# Smarttree_BMS_6.net
KiCad netlist of a schematic drawn in EAGLE
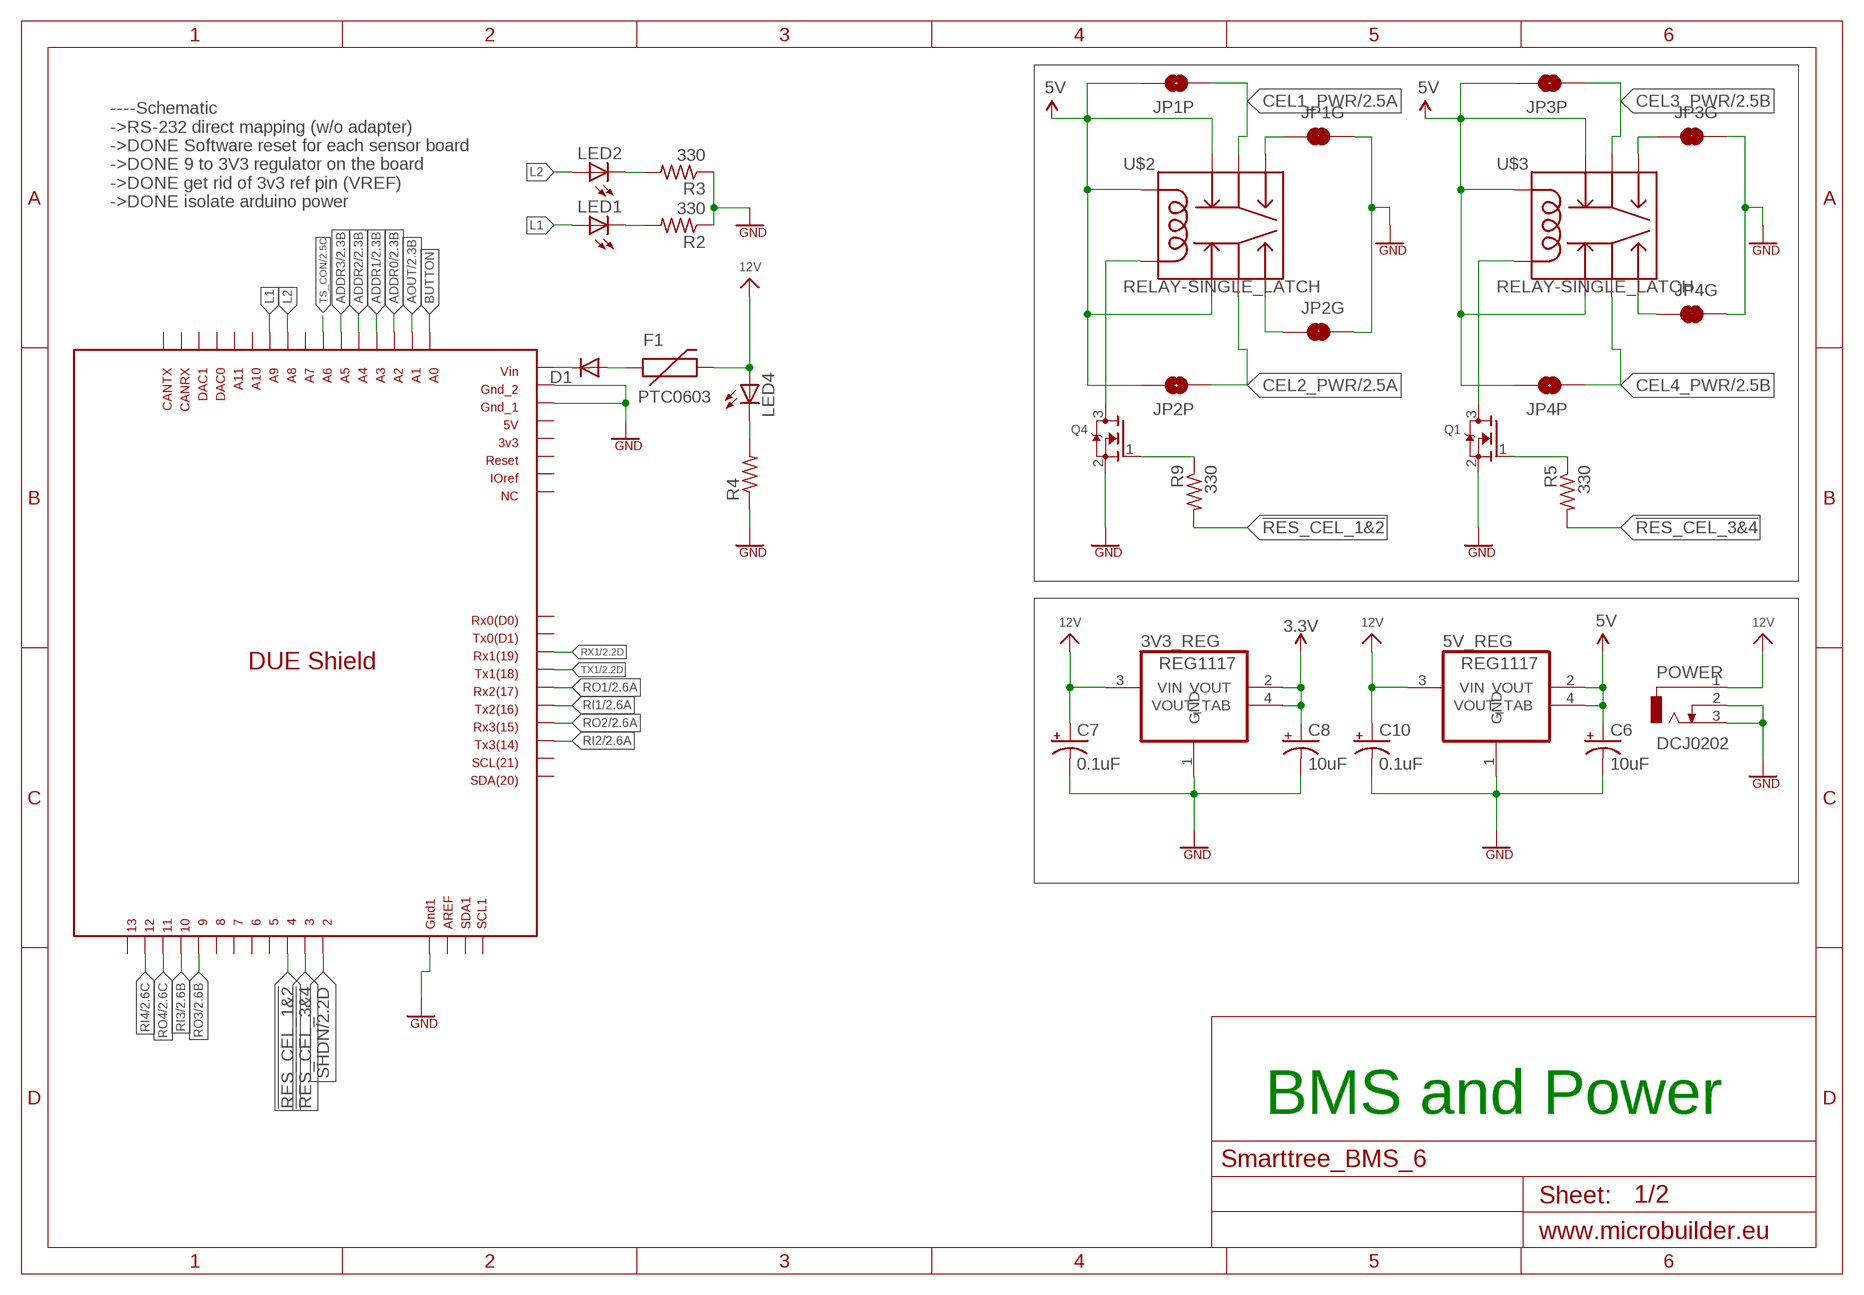
[diagram p0: schematic, sheet 1]
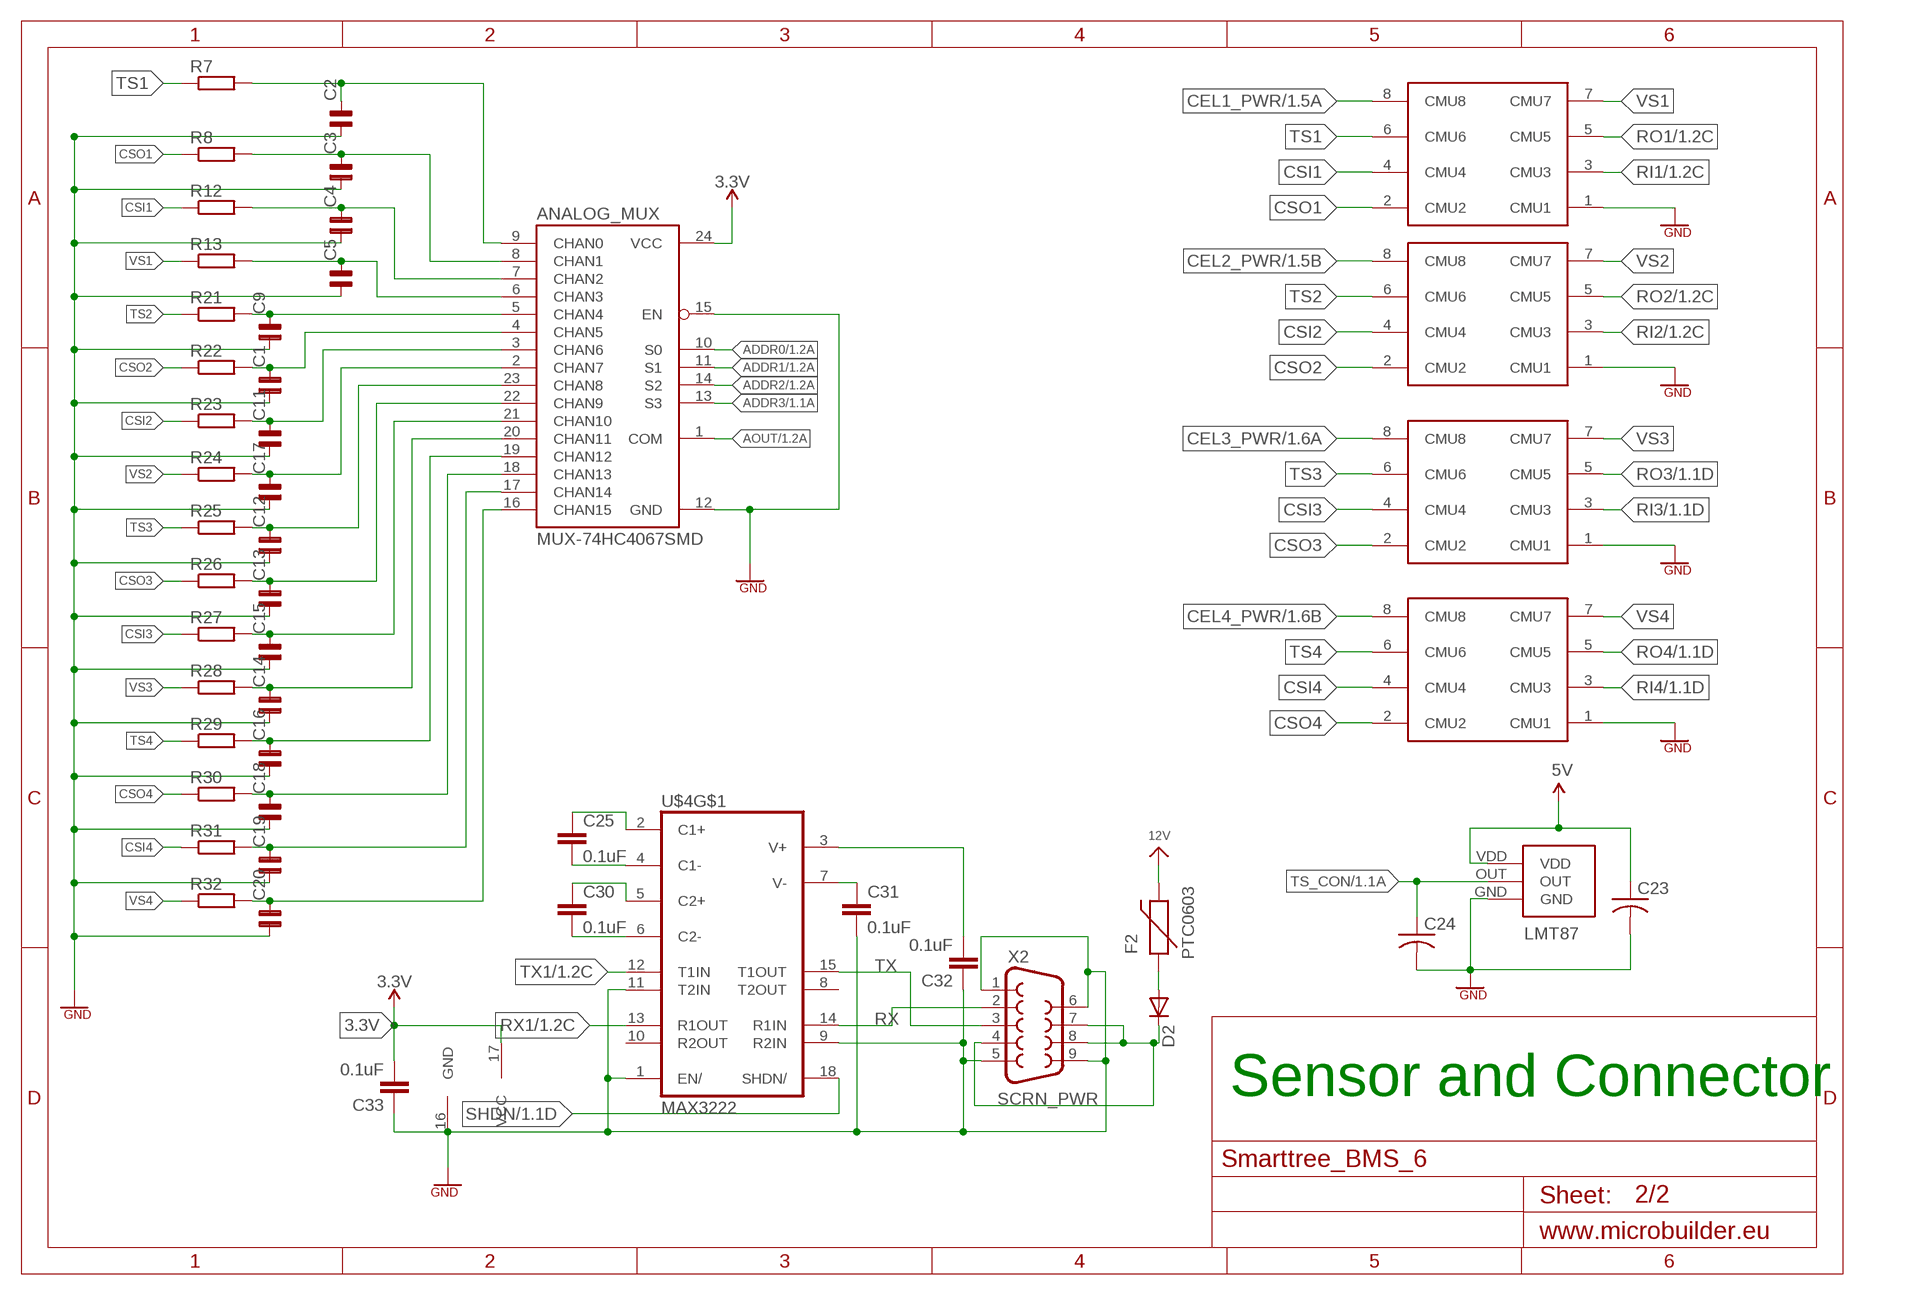
[diagram p1: schematic, sheet 2]

(export (version "E")
  (design (tool "Eeschema 10.0.6"))
  (components
    (comp (ref "ANALOG_MUX")
      (value "MUX-74HC4067SMD")
      (footprint "eagle-import:SSOP24")
      (libsource (lib "eagle-import") (part "MUX-74HC4067SMD"))
    )
    (comp (ref "C1")
      (value "C-NP-SMD-0805")
      (footprint "eagle-import:C-0805")
      (libsource (lib "eagle-import") (part "C-NP-SMD-0805"))
    )
    (comp (ref "C2")
      (value "C-NP-SMD-0805")
      (footprint "eagle-import:C-0805")
      (libsource (lib "eagle-import") (part "C-NP-SMD-0805"))
    )
    (comp (ref "C3")
      (value "C-NP-SMD-0805")
      (footprint "eagle-import:C-0805")
      (libsource (lib "eagle-import") (part "C-NP-SMD-0805"))
    )
    (comp (ref "C4")
      (value "C-NP-SMD-0805")
      (footprint "eagle-import:C-0805")
      (libsource (lib "eagle-import") (part "C-NP-SMD-0805"))
    )
    (comp (ref "C5")
      (value "C-NP-SMD-0805")
      (footprint "eagle-import:C-0805")
      (libsource (lib "eagle-import") (part "C-NP-SMD-0805"))
    )
    (comp (ref "C9")
      (value "C-NP-SMD-0805")
      (footprint "eagle-import:C-0805")
      (libsource (lib "eagle-import") (part "C-NP-SMD-0805"))
    )
    (comp (ref "C11")
      (value "C-NP-SMD-0805")
      (footprint "eagle-import:C-0805")
      (libsource (lib "eagle-import") (part "C-NP-SMD-0805"))
    )
    (comp (ref "C12")
      (value "C-NP-SMD-0805")
      (footprint "eagle-import:C-0805")
      (libsource (lib "eagle-import") (part "C-NP-SMD-0805"))
    )
    (comp (ref "C13")
      (value "C-NP-SMD-0805")
      (footprint "eagle-import:C-0805")
      (libsource (lib "eagle-import") (part "C-NP-SMD-0805"))
    )
    (comp (ref "C14")
      (value "C-NP-SMD-0805")
      (footprint "eagle-import:C-0805")
      (libsource (lib "eagle-import") (part "C-NP-SMD-0805"))
    )
    (comp (ref "C15")
      (value "C-NP-SMD-0805")
      (footprint "eagle-import:C-0805")
      (libsource (lib "eagle-import") (part "C-NP-SMD-0805"))
    )
    (comp (ref "C16")
      (value "C-NP-SMD-0805")
      (footprint "eagle-import:C-0805")
      (libsource (lib "eagle-import") (part "C-NP-SMD-0805"))
    )
    (comp (ref "C17")
      (value "C-NP-SMD-0805")
      (footprint "eagle-import:C-0805")
      (libsource (lib "eagle-import") (part "C-NP-SMD-0805"))
    )
    (comp (ref "C18")
      (value "C-NP-SMD-0805")
      (footprint "eagle-import:C-0805")
      (libsource (lib "eagle-import") (part "C-NP-SMD-0805"))
    )
    (comp (ref "C19")
      (value "C-NP-SMD-0805")
      (footprint "eagle-import:C-0805")
      (libsource (lib "eagle-import") (part "C-NP-SMD-0805"))
    )
    (comp (ref "C20")
      (value "C-NP-SMD-0805")
      (footprint "eagle-import:C-0805")
      (libsource (lib "eagle-import") (part "C-NP-SMD-0805"))
    )
    (comp (ref "C23")
      (value "C-USC0805")
      (footprint "eagle-import:C0805")
      (libsource (lib "eagle-import") (part "C-USC0805"))
    )
    (comp (ref "C24")
      (value "C-USC0805")
      (footprint "eagle-import:C0805")
      (libsource (lib "eagle-import") (part "C-USC0805"))
    )
    (comp (ref "C25")
      (value "0.1uF")
      (footprint "eagle-import:0603-CAP")
      (libsource (lib "eagle-import") (part "CAP0603-CAP"))
    )
    (comp (ref "C30")
      (value "0.1uF")
      (footprint "eagle-import:0603-CAP")
      (libsource (lib "eagle-import") (part "CAP0603-CAP"))
    )
    (comp (ref "C31")
      (value "0.1uF")
      (footprint "eagle-import:0603-CAP")
      (libsource (lib "eagle-import") (part "CAP0603-CAP"))
    )
    (comp (ref "C32")
      (value "0.1uF")
      (footprint "eagle-import:0603-CAP")
      (libsource (lib "eagle-import") (part "CAP0603-CAP"))
    )
    (comp (ref "C33")
      (value "0.1uF")
      (footprint "eagle-import:0603-CAP")
      (libsource (lib "eagle-import") (part "CAP0603-CAP"))
    )
    (comp (ref "CEL1")
      (value "8PINCONN")
      (footprint "eagle-import:8PINCONN")
      (libsource (lib "eagle-import") (part "8PINCONN"))
    )
    (comp (ref "CEL2")
      (value "8PINCONN")
      (footprint "eagle-import:8PINCONN")
      (libsource (lib "eagle-import") (part "8PINCONN"))
    )
    (comp (ref "CEL3")
      (value "8PINCONN")
      (footprint "eagle-import:8PINCONN")
      (libsource (lib "eagle-import") (part "8PINCONN"))
    )
    (comp (ref "CEL4")
      (value "8PINCONN")
      (footprint "eagle-import:8PINCONN")
      (libsource (lib "eagle-import") (part "8PINCONN"))
    )
    (comp (ref "D2")
      (value "DIODE-SOD106-R")
      (footprint "eagle-import:SOD106-R")
      (libsource (lib "eagle-import") (part "DIODE-SOD106-R"))
    )
    (comp (ref "F2")
      (value "PTC0603")
      (footprint "eagle-import:0603")
      (libsource (lib "eagle-import") (part "PTC0603"))
    )
    (comp (ref "LMT87")
      (value "LMT87_PAC")
      (footprint "eagle-import:LMT87_TO")
      (libsource (lib "eagle-import") (part "LMT87_PAC"))
    )
    (comp (ref "R7")
      (value "R-EU_R0805W")
      (footprint "eagle-import:R0805W")
      (libsource (lib "eagle-import") (part "R-EU_R0805W"))
    )
    (comp (ref "R8")
      (value "R-EU_R0805W")
      (footprint "eagle-import:R0805W")
      (libsource (lib "eagle-import") (part "R-EU_R0805W"))
    )
    (comp (ref "R12")
      (value "R-EU_R0805W")
      (footprint "eagle-import:R0805W")
      (libsource (lib "eagle-import") (part "R-EU_R0805W"))
    )
    (comp (ref "R13")
      (value "R-EU_R0805W")
      (footprint "eagle-import:R0805W")
      (libsource (lib "eagle-import") (part "R-EU_R0805W"))
    )
    (comp (ref "R21")
      (value "R-EU_R0805W")
      (footprint "eagle-import:R0805W")
      (libsource (lib "eagle-import") (part "R-EU_R0805W"))
    )
    (comp (ref "R22")
      (value "R-EU_R0805W")
      (footprint "eagle-import:R0805W")
      (libsource (lib "eagle-import") (part "R-EU_R0805W"))
    )
    (comp (ref "R23")
      (value "R-EU_R0805W")
      (footprint "eagle-import:R0805W")
      (libsource (lib "eagle-import") (part "R-EU_R0805W"))
    )
    (comp (ref "R24")
      (value "R-EU_R0805W")
      (footprint "eagle-import:R0805W")
      (libsource (lib "eagle-import") (part "R-EU_R0805W"))
    )
    (comp (ref "R25")
      (value "R-EU_R0805W")
      (footprint "eagle-import:R0805W")
      (libsource (lib "eagle-import") (part "R-EU_R0805W"))
    )
    (comp (ref "R26")
      (value "R-EU_R0805W")
      (footprint "eagle-import:R0805W")
      (libsource (lib "eagle-import") (part "R-EU_R0805W"))
    )
    (comp (ref "R27")
      (value "R-EU_R0805W")
      (footprint "eagle-import:R0805W")
      (libsource (lib "eagle-import") (part "R-EU_R0805W"))
    )
    (comp (ref "R28")
      (value "R-EU_R0805W")
      (footprint "eagle-import:R0805W")
      (libsource (lib "eagle-import") (part "R-EU_R0805W"))
    )
    (comp (ref "R29")
      (value "R-EU_R0805W")
      (footprint "eagle-import:R0805W")
      (libsource (lib "eagle-import") (part "R-EU_R0805W"))
    )
    (comp (ref "R30")
      (value "R-EU_R0805W")
      (footprint "eagle-import:R0805W")
      (libsource (lib "eagle-import") (part "R-EU_R0805W"))
    )
    (comp (ref "R31")
      (value "R-EU_R0805W")
      (footprint "eagle-import:R0805W")
      (libsource (lib "eagle-import") (part "R-EU_R0805W"))
    )
    (comp (ref "R32")
      (value "R-EU_R0805W")
      (footprint "eagle-import:R0805W")
      (libsource (lib "eagle-import") (part "R-EU_R0805W"))
    )
    (comp (ref "U$4")
      (value "MAX3222")
      (footprint "eagle-import:SO18")
      (libsource (lib "eagle-import") (part "MAX3222"))
    )
    (comp (ref "X2")
      (value "DB9MALE")
      (footprint "eagle-import:DB9_MALE")
      (libsource (lib "eagle-import") (part "DB9MALE"))
    )
    (comp (ref "3V3_REG")
      (value "REG1117")
      (footprint "eagle-import:SOT223")
      (libsource (lib "eagle-import") (part "REG1117"))
    )
    (comp (ref "5V_REG")
      (value "REG1117")
      (footprint "eagle-import:SOT223")
      (libsource (lib "eagle-import") (part "REG1117"))
    )
    (comp (ref "C6")
      (value "10uF")
      (footprint "eagle-import:EIA3216")
      (libsource (lib "eagle-import") (part "10UF-TANT"))
    )
    (comp (ref "C7")
      (value "0.1uF")
      (footprint "eagle-import:EIA3216")
      (libsource (lib "eagle-import") (part "10UF-TANT"))
    )
    (comp (ref "C8")
      (value "10uF")
      (footprint "eagle-import:EIA3216")
      (libsource (lib "eagle-import") (part "10UF-TANT"))
    )
    (comp (ref "C10")
      (value "0.1uF")
      (footprint "eagle-import:EIA3216")
      (libsource (lib "eagle-import") (part "10UF-TANT"))
    )
    (comp (ref "D1")
      (value "DIODE-SOD106-R")
      (footprint "eagle-import:SOD106-R")
      (libsource (lib "eagle-import") (part "DIODE-SOD106-R"))
    )
    (comp (ref "F1")
      (value "PTC0603")
      (footprint "eagle-import:0603")
      (libsource (lib "eagle-import") (part "PTC0603"))
    )
    (comp (ref "JP1G")
      (value "JUMPER-SMT_2_NC_TRACE_SILK")
      (footprint "eagle-import:SMT-JUMPER_2_NC_TRACE_SILK")
      (libsource (lib "eagle-import") (part "JUMPER-SMT_2_NC_TRACE_SILK"))
    )
    (comp (ref "JP1P")
      (value "JUMPER-SMT_2_NO_SILK")
      (footprint "eagle-import:SMT-JUMPER_2_NO_SILK")
      (libsource (lib "eagle-import") (part "JUMPER-SMT_2_NO_SILK"))
    )
    (comp (ref "JP2G")
      (value "JUMPER-SMT_2_NC_TRACE_SILK")
      (footprint "eagle-import:SMT-JUMPER_2_NC_TRACE_SILK")
      (libsource (lib "eagle-import") (part "JUMPER-SMT_2_NC_TRACE_SILK"))
    )
    (comp (ref "JP2P")
      (value "JUMPER-SMT_2_NO_SILK")
      (footprint "eagle-import:SMT-JUMPER_2_NO_SILK")
      (libsource (lib "eagle-import") (part "JUMPER-SMT_2_NO_SILK"))
    )
    (comp (ref "JP3G")
      (value "JUMPER-SMT_2_NC_TRACE_SILK")
      (footprint "eagle-import:SMT-JUMPER_2_NC_TRACE_SILK")
      (libsource (lib "eagle-import") (part "JUMPER-SMT_2_NC_TRACE_SILK"))
    )
    (comp (ref "JP3P")
      (value "JUMPER-SMT_2_NO_SILK")
      (footprint "eagle-import:SMT-JUMPER_2_NO_SILK")
      (libsource (lib "eagle-import") (part "JUMPER-SMT_2_NO_SILK"))
    )
    (comp (ref "JP4G")
      (value "JUMPER-SMT_2_NC_TRACE_SILK")
      (footprint "eagle-import:SMT-JUMPER_2_NC_TRACE_SILK")
      (libsource (lib "eagle-import") (part "JUMPER-SMT_2_NC_TRACE_SILK"))
    )
    (comp (ref "JP4P")
      (value "JUMPER-SMT_2_NO_SILK")
      (footprint "eagle-import:SMT-JUMPER_2_NO_SILK")
      (libsource (lib "eagle-import") (part "JUMPER-SMT_2_NO_SILK"))
    )
    (comp (ref "LED1")
      (value "LED-YELLOW0603")
      (footprint "eagle-import:LED-0603")
      (libsource (lib "eagle-import") (part "LED-YELLOW0603"))
    )
    (comp (ref "LED2")
      (value "LED-YELLOW0603")
      (footprint "eagle-import:LED-0603")
      (libsource (lib "eagle-import") (part "LED-YELLOW0603"))
    )
    (comp (ref "LED4")
      (value "LED-YELLOW0603")
      (footprint "eagle-import:LED-0603")
      (libsource (lib "eagle-import") (part "LED-YELLOW0603"))
    )
    (comp (ref "POWER")
      (value "DCJ0202")
      (footprint "eagle-import:DCJ0202")
      (libsource (lib "eagle-import") (part "DCJ0202"))
    )
    (comp (ref "Q1")
      (value "MOSFET-NREFLOW")
      (footprint "eagle-import:SOT23")
      (libsource (lib "eagle-import") (part "MOSFET-NREFLOW"))
    )
    (comp (ref "Q4")
      (value "MOSFET-NREFLOW")
      (footprint "eagle-import:SOT23")
      (libsource (lib "eagle-import") (part "MOSFET-NREFLOW"))
    )
    (comp (ref "R2")
      (value "330")
      (footprint "eagle-import:M0805")
      (libsource (lib "eagle-import") (part "R-US_M0805"))
    )
    (comp (ref "R3")
      (value "330")
      (footprint "eagle-import:M0805")
      (libsource (lib "eagle-import") (part "R-US_M0805"))
    )
    (comp (ref "R4")
      (value "R-US_M0805")
      (footprint "eagle-import:M0805")
      (libsource (lib "eagle-import") (part "R-US_M0805"))
    )
    (comp (ref "R5")
      (value "330")
      (footprint "eagle-import:R0805")
      (libsource (lib "eagle-import") (part "R-US_R0805"))
    )
    (comp (ref "R9")
      (value "330")
      (footprint "eagle-import:R0805")
      (libsource (lib "eagle-import") (part "R-US_R0805"))
    )
    (comp (ref "U$1")
      (value "DUE(OUTLINE)")
      (footprint "eagle-import:DUE(NORMAL)")
      (libsource (lib "eagle-import") (part "DUE(OUTLINE)"))
    )
    (comp (ref "U$2")
      (value "RELAY-SINGLE_LATCH")
      (footprint "eagle-import:RELAY-EE2")
      (libsource (lib "eagle-import") (part "RELAY-SINGLE_LATCH"))
    )
    (comp (ref "U$3")
      (value "RELAY-SINGLE_LATCH")
      (footprint "eagle-import:RELAY-EE2")
      (libsource (lib "eagle-import") (part "RELAY-SINGLE_LATCH"))
    )
  )
  (nets
    (net (code "1") (name "3.3V") (class "Default")
      (node (ref "3V3_REG") (pin "2") (pinfunction "VOUT_2") (pintype "output"))
      (node (ref "3V3_REG") (pin "4") (pinfunction "VOUT_TAB_4") (pintype "bidirectional"))
      (node (ref "ANALOG_MUX") (pin "24") (pinfunction "VCC_24") (pintype "bidirectional"))
      (node (ref "C33") (pin "2") (pinfunction "2_2") (pintype "passive"))
      (node (ref "C8") (pin "A") (pinfunction "+_A") (pintype "passive"))
      (node (ref "U$4") (pin "17") (pinfunction "VCC_17") (pintype "bidirectional"))
    )
    (net (code "2") (name "5V") (class "Default")
      (node (ref "5V_REG") (pin "2") (pinfunction "VOUT_2") (pintype "output"))
      (node (ref "5V_REG") (pin "4") (pinfunction "VOUT_TAB_4") (pintype "bidirectional"))
      (node (ref "C23") (pin "1") (pinfunction "1_1") (pintype "passive"))
      (node (ref "C6") (pin "A") (pinfunction "+_A") (pintype "passive"))
      (node (ref "JP1P") (pin "2") (pinfunction "2_2") (pintype "passive"))
      (node (ref "JP2P") (pin "2") (pinfunction "2_2") (pintype "passive"))
      (node (ref "JP3P") (pin "2") (pinfunction "2_2") (pintype "passive"))
      (node (ref "JP4P") (pin "2") (pinfunction "2_2") (pintype "passive"))
      (node (ref "LMT87") (pin "VDD") (pinfunction "VDD_VDD") (pintype "bidirectional"))
      (node (ref "U$2") (pin "P$1") (pinfunction "COIL1_P$1") (pintype "bidirectional"))
      (node (ref "U$2") (pin "P$10") (pinfunction "P$10_P$10") (pintype "bidirectional"))
      (node (ref "U$2") (pin "P$3") (pinfunction "P$3_P$3") (pintype "bidirectional"))
      (node (ref "U$3") (pin "P$1") (pinfunction "COIL1_P$1") (pintype "bidirectional"))
      (node (ref "U$3") (pin "P$10") (pinfunction "P$10_P$10") (pintype "bidirectional"))
      (node (ref "U$3") (pin "P$3") (pinfunction "P$3_P$3") (pintype "bidirectional"))
    )
    (net (code "3") (name "12V") (class "Default")
      (node (ref "3V3_REG") (pin "3") (pinfunction "VIN_3") (pintype "input"))
      (node (ref "5V_REG") (pin "3") (pinfunction "VIN_3") (pintype "input"))
      (node (ref "C10") (pin "A") (pinfunction "+_A") (pintype "passive"))
      (node (ref "C7") (pin "A") (pinfunction "+_A") (pintype "passive"))
      (node (ref "F1") (pin "2") (pinfunction "2_2") (pintype "bidirectional"))
      (node (ref "F2") (pin "2") (pinfunction "2_2") (pintype "bidirectional"))
      (node (ref "LED4") (pin "A") (pinfunction "A_A") (pintype "passive"))
      (node (ref "POWER") (pin "1") (pinfunction "1_1") (pintype "passive"))
    )
    (net (code "4") (name "ADDR0") (class "Default")
      (node (ref "ANALOG_MUX") (pin "10") (pinfunction "S0_10") (pintype "input"))
      (node (ref "U$1") (pin "A2") (pinfunction "A2_A2") (pintype "bidirectional"))
    )
    (net (code "5") (name "ADDR1") (class "Default")
      (node (ref "ANALOG_MUX") (pin "11") (pinfunction "S1_11") (pintype "input"))
      (node (ref "U$1") (pin "A3") (pinfunction "A3_A3") (pintype "bidirectional"))
    )
    (net (code "6") (name "ADDR2") (class "Default")
      (node (ref "ANALOG_MUX") (pin "14") (pinfunction "S2_14") (pintype "input"))
      (node (ref "U$1") (pin "A4") (pinfunction "A4_A4") (pintype "bidirectional"))
    )
    (net (code "7") (name "ADDR3") (class "Default")
      (node (ref "ANALOG_MUX") (pin "13") (pinfunction "S3_13") (pintype "input"))
      (node (ref "U$1") (pin "A5") (pinfunction "A5_A5") (pintype "bidirectional"))
    )
    (net (code "8") (name "AOUT") (class "Default")
      (node (ref "ANALOG_MUX") (pin "1") (pinfunction "COM_1") (pintype "bidirectional"))
      (node (ref "U$1") (pin "A1") (pinfunction "A1_A1") (pintype "bidirectional"))
    )
    (net (code "9") (name "BUTTON") (class "Default")
      (node (ref "U$1") (pin "A0") (pinfunction "A0_A0") (pintype "bidirectional"))
    )
    (net (code "10") (name "CEL1_PWR") (class "Default")
      (node (ref "CEL1") (pin "8") (pinfunction "CMU8_8") (pintype "bidirectional"))
      (node (ref "JP1P") (pin "1") (pinfunction "1_1") (pintype "passive"))
      (node (ref "U$2") (pin "P$4") (pinfunction "P$4_P$4") (pintype "bidirectional"))
    )
    (net (code "11") (name "CEL2_PWR") (class "Default")
      (node (ref "CEL2") (pin "8") (pinfunction "CMU8_8") (pintype "bidirectional"))
      (node (ref "JP2P") (pin "1") (pinfunction "1_1") (pintype "passive"))
      (node (ref "U$2") (pin "P$9") (pinfunction "P$9_P$9") (pintype "bidirectional"))
    )
    (net (code "12") (name "CEL3_PWR") (class "Default")
      (node (ref "CEL3") (pin "8") (pinfunction "CMU8_8") (pintype "bidirectional"))
      (node (ref "JP3P") (pin "1") (pinfunction "1_1") (pintype "passive"))
      (node (ref "U$3") (pin "P$4") (pinfunction "P$4_P$4") (pintype "bidirectional"))
    )
    (net (code "13") (name "CEL4_PWR") (class "Default")
      (node (ref "CEL4") (pin "8") (pinfunction "CMU8_8") (pintype "bidirectional"))
      (node (ref "JP4P") (pin "1") (pinfunction "1_1") (pintype "passive"))
      (node (ref "U$3") (pin "P$9") (pinfunction "P$9_P$9") (pintype "bidirectional"))
    )
    (net (code "14") (name "CSI1") (class "Default")
      (node (ref "CEL1") (pin "4") (pinfunction "CMU4_4") (pintype "bidirectional"))
      (node (ref "R12") (pin "1") (pinfunction "1_1") (pintype "passive"))
    )
    (net (code "15") (name "CSI2") (class "Default")
      (node (ref "CEL2") (pin "4") (pinfunction "CMU4_4") (pintype "bidirectional"))
      (node (ref "R23") (pin "1") (pinfunction "1_1") (pintype "passive"))
    )
    (net (code "16") (name "CSI3") (class "Default")
      (node (ref "CEL3") (pin "4") (pinfunction "CMU4_4") (pintype "bidirectional"))
      (node (ref "R27") (pin "1") (pinfunction "1_1") (pintype "passive"))
    )
    (net (code "17") (name "CSI4") (class "Default")
      (node (ref "CEL4") (pin "4") (pinfunction "CMU4_4") (pintype "bidirectional"))
      (node (ref "R31") (pin "1") (pinfunction "1_1") (pintype "passive"))
    )
    (net (code "18") (name "CSO1") (class "Default")
      (node (ref "CEL1") (pin "2") (pinfunction "CMU2_2") (pintype "bidirectional"))
      (node (ref "R8") (pin "1") (pinfunction "1_1") (pintype "passive"))
    )
    (net (code "19") (name "CSO2") (class "Default")
      (node (ref "CEL2") (pin "2") (pinfunction "CMU2_2") (pintype "bidirectional"))
      (node (ref "R22") (pin "1") (pinfunction "1_1") (pintype "passive"))
    )
    (net (code "20") (name "CSO3") (class "Default")
      (node (ref "CEL3") (pin "2") (pinfunction "CMU2_2") (pintype "bidirectional"))
      (node (ref "R26") (pin "1") (pinfunction "1_1") (pintype "passive"))
    )
    (net (code "21") (name "CSO4") (class "Default")
      (node (ref "CEL4") (pin "2") (pinfunction "CMU2_2") (pintype "bidirectional"))
      (node (ref "R30") (pin "1") (pinfunction "1_1") (pintype "passive"))
    )
    (net (code "22") (name "GND") (class "Default")
      (node (ref "3V3_REG") (pin "1") (pinfunction "GND_1") (pintype "power_in"))
      (node (ref "5V_REG") (pin "1") (pinfunction "GND_1") (pintype "power_in"))
      (node (ref "ANALOG_MUX") (pin "12") (pinfunction "GND_12") (pintype "bidirectional"))
      (node (ref "ANALOG_MUX") (pin "15") (pinfunction "EN_15") (pintype "input"))
      (node (ref "C1") (pin "1") (pinfunction "1_1") (pintype "passive"))
      (node (ref "C10") (pin "C") (pinfunction "-_C") (pintype "passive"))
      (node (ref "C11") (pin "1") (pinfunction "1_1") (pintype "passive"))
      (node (ref "C12") (pin "1") (pinfunction "1_1") (pintype "passive"))
      (node (ref "C13") (pin "1") (pinfunction "1_1") (pintype "passive"))
      (node (ref "C14") (pin "1") (pinfunction "1_1") (pintype "passive"))
      (node (ref "C15") (pin "1") (pinfunction "1_1") (pintype "passive"))
      (node (ref "C16") (pin "1") (pinfunction "1_1") (pintype "passive"))
      (node (ref "C17") (pin "1") (pinfunction "1_1") (pintype "passive"))
      (node (ref "C18") (pin "1") (pinfunction "1_1") (pintype "passive"))
      (node (ref "C19") (pin "1") (pinfunction "1_1") (pintype "passive"))
      (node (ref "C2") (pin "1") (pinfunction "1_1") (pintype "passive"))
      (node (ref "C20") (pin "1") (pinfunction "1_1") (pintype "passive"))
      (node (ref "C23") (pin "2") (pinfunction "2_2") (pintype "passive"))
      (node (ref "C24") (pin "2") (pinfunction "2_2") (pintype "passive"))
      (node (ref "C3") (pin "1") (pinfunction "1_1") (pintype "passive"))
      (node (ref "C31") (pin "2") (pinfunction "2_2") (pintype "passive"))
      (node (ref "C32") (pin "1") (pinfunction "1_1") (pintype "passive"))
      (node (ref "C33") (pin "1") (pinfunction "1_1") (pintype "passive"))
      (node (ref "C4") (pin "1") (pinfunction "1_1") (pintype "passive"))
      (node (ref "C5") (pin "1") (pinfunction "1_1") (pintype "passive"))
      (node (ref "C6") (pin "C") (pinfunction "-_C") (pintype "passive"))
      (node (ref "C7") (pin "C") (pinfunction "-_C") (pintype "passive"))
      (node (ref "C8") (pin "C") (pinfunction "-_C") (pintype "passive"))
      (node (ref "C9") (pin "1") (pinfunction "1_1") (pintype "passive"))
      (node (ref "CEL1") (pin "1") (pinfunction "CMU1_1") (pintype "bidirectional"))
      (node (ref "CEL2") (pin "1") (pinfunction "CMU1_1") (pintype "bidirectional"))
      (node (ref "CEL3") (pin "1") (pinfunction "CMU1_1") (pintype "bidirectional"))
      (node (ref "CEL4") (pin "1") (pinfunction "CMU1_1") (pintype "bidirectional"))
      (node (ref "JP1G") (pin "2") (pinfunction "2_2") (pintype "passive"))
      (node (ref "JP2G") (pin "2") (pinfunction "2_2") (pintype "passive"))
      (node (ref "JP3G") (pin "2") (pinfunction "2_2") (pintype "passive"))
      (node (ref "JP4G") (pin "2") (pinfunction "2_2") (pintype "passive"))
      (node (ref "LMT87") (pin "GND") (pinfunction "GND_GND") (pintype "bidirectional"))
      (node (ref "POWER") (pin "2") (pinfunction "2_2") (pintype "passive"))
      (node (ref "POWER") (pin "3") (pinfunction "3_3") (pintype "passive"))
      (node (ref "Q1") (pin "2") (pinfunction "S_2") (pintype "bidirectional"))
      (node (ref "Q4") (pin "2") (pinfunction "S_2") (pintype "bidirectional"))
      (node (ref "R2") (pin "1") (pinfunction "1_1") (pintype "passive"))
      (node (ref "R3") (pin "1") (pinfunction "1_1") (pintype "passive"))
      (node (ref "R4") (pin "1") (pinfunction "1_1") (pintype "passive"))
      (node (ref "U$1") (pin "GND1") (pinfunction "GND1_GND1") (pintype "bidirectional"))
      (node (ref "U$1") (pin "GND_1") (pinfunction "GND_1_GND_1") (pintype "bidirectional"))
      (node (ref "U$1") (pin "GND_2") (pinfunction "GND_2_GND_2") (pintype "bidirectional"))
      (node (ref "U$4") (pin "1") (pinfunction "EN/_1") (pintype "input"))
      (node (ref "U$4") (pin "11") (pinfunction "T2IN_11") (pintype "input"))
      (node (ref "U$4") (pin "16") (pinfunction "GND_16") (pintype "bidirectional"))
      (node (ref "U$4") (pin "9") (pinfunction "R2IN_9") (pintype "input"))
      (node (ref "X2") (pin "1") (pinfunction "1_1") (pintype "passive"))
      (node (ref "X2") (pin "5") (pinfunction "5_5") (pintype "passive"))
      (node (ref "X2") (pin "6") (pinfunction "6_6") (pintype "passive"))
      (node (ref "X2") (pin "9") (pinfunction "9_9") (pintype "passive"))
    )
    (net (code "23") (name "L1") (class "Default")
      (node (ref "LED1") (pin "A") (pinfunction "A_A") (pintype "passive"))
      (node (ref "U$1") (pin "A9") (pinfunction "A9_A9") (pintype "bidirectional"))
    )
    (net (code "24") (name "L2") (class "Default")
      (node (ref "LED2") (pin "A") (pinfunction "A_A") (pintype "passive"))
      (node (ref "U$1") (pin "A8") (pinfunction "A8_A8") (pintype "bidirectional"))
    )
    (net (code "25") (name "Net-(ANALOG_MUX-CHAN0)") (class "Default")
      (node (ref "ANALOG_MUX") (pin "9") (pinfunction "CHAN0_9") (pintype "bidirectional"))
      (node (ref "C2") (pin "2") (pinfunction "2_2") (pintype "passive"))
      (node (ref "R7") (pin "2") (pinfunction "2_2") (pintype "passive"))
    )
    (net (code "26") (name "Net-(ANALOG_MUX-CHAN1)") (class "Default")
      (node (ref "ANALOG_MUX") (pin "8") (pinfunction "CHAN1_8") (pintype "bidirectional"))
      (node (ref "C3") (pin "2") (pinfunction "2_2") (pintype "passive"))
      (node (ref "R8") (pin "2") (pinfunction "2_2") (pintype "passive"))
    )
    (net (code "27") (name "Net-(ANALOG_MUX-CHAN2)") (class "Default")
      (node (ref "ANALOG_MUX") (pin "7") (pinfunction "CHAN2_7") (pintype "bidirectional"))
      (node (ref "C4") (pin "2") (pinfunction "2_2") (pintype "passive"))
      (node (ref "R12") (pin "2") (pinfunction "2_2") (pintype "passive"))
    )
    (net (code "28") (name "Net-(ANALOG_MUX-CHAN3)") (class "Default")
      (node (ref "ANALOG_MUX") (pin "6") (pinfunction "CHAN3_6") (pintype "bidirectional"))
      (node (ref "C5") (pin "2") (pinfunction "2_2") (pintype "passive"))
      (node (ref "R13") (pin "2") (pinfunction "2_2") (pintype "passive"))
    )
    (net (code "29") (name "Net-(ANALOG_MUX-CHAN4)") (class "Default")
      (node (ref "ANALOG_MUX") (pin "5") (pinfunction "CHAN4_5") (pintype "bidirectional"))
      (node (ref "C9") (pin "2") (pinfunction "2_2") (pintype "passive"))
      (node (ref "R21") (pin "2") (pinfunction "2_2") (pintype "passive"))
    )
    (net (code "30") (name "Net-(ANALOG_MUX-CHAN5)") (class "Default")
      (node (ref "ANALOG_MUX") (pin "4") (pinfunction "CHAN5_4") (pintype "bidirectional"))
      (node (ref "C1") (pin "2") (pinfunction "2_2") (pintype "passive"))
      (node (ref "R22") (pin "2") (pinfunction "2_2") (pintype "passive"))
    )
    (net (code "31") (name "Net-(ANALOG_MUX-CHAN6)") (class "Default")
      (node (ref "ANALOG_MUX") (pin "3") (pinfunction "CHAN6_3") (pintype "bidirectional"))
      (node (ref "C11") (pin "2") (pinfunction "2_2") (pintype "passive"))
      (node (ref "R23") (pin "2") (pinfunction "2_2") (pintype "passive"))
    )
    (net (code "32") (name "Net-(ANALOG_MUX-CHAN7)") (class "Default")
      (node (ref "ANALOG_MUX") (pin "2") (pinfunction "CHAN7_2") (pintype "bidirectional"))
      (node (ref "C17") (pin "2") (pinfunction "2_2") (pintype "passive"))
      (node (ref "R24") (pin "2") (pinfunction "2_2") (pintype "passive"))
    )
    (net (code "33") (name "Net-(ANALOG_MUX-CHAN8)") (class "Default")
      (node (ref "ANALOG_MUX") (pin "23") (pinfunction "CHAN8_23") (pintype "bidirectional"))
      (node (ref "C12") (pin "2") (pinfunction "2_2") (pintype "passive"))
      (node (ref "R25") (pin "2") (pinfunction "2_2") (pintype "passive"))
    )
    (net (code "34") (name "Net-(ANALOG_MUX-CHAN9)") (class "Default")
      (node (ref "ANALOG_MUX") (pin "22") (pinfunction "CHAN9_22") (pintype "bidirectional"))
      (node (ref "C13") (pin "2") (pinfunction "2_2") (pintype "passive"))
      (node (ref "R26") (pin "2") (pinfunction "2_2") (pintype "passive"))
    )
    (net (code "35") (name "Net-(ANALOG_MUX-CHAN10)") (class "Default")
      (node (ref "ANALOG_MUX") (pin "21") (pinfunction "CHAN10_21") (pintype "bidirectional"))
      (node (ref "C15") (pin "2") (pinfunction "2_2") (pintype "passive"))
      (node (ref "R27") (pin "2") (pinfunction "2_2") (pintype "passive"))
    )
    (net (code "36") (name "Net-(ANALOG_MUX-CHAN11)") (class "Default")
      (node (ref "ANALOG_MUX") (pin "20") (pinfunction "CHAN11_20") (pintype "bidirectional"))
      (node (ref "C14") (pin "2") (pinfunction "2_2") (pintype "passive"))
      (node (ref "R28") (pin "2") (pinfunction "2_2") (pintype "passive"))
    )
    (net (code "37") (name "Net-(ANALOG_MUX-CHAN12)") (class "Default")
      (node (ref "ANALOG_MUX") (pin "19") (pinfunction "CHAN12_19") (pintype "bidirectional"))
      (node (ref "C16") (pin "2") (pinfunction "2_2") (pintype "passive"))
      (node (ref "R29") (pin "2") (pinfunction "2_2") (pintype "passive"))
    )
    (net (code "38") (name "Net-(ANALOG_MUX-CHAN13)") (class "Default")
      (node (ref "ANALOG_MUX") (pin "18") (pinfunction "CHAN13_18") (pintype "bidirectional"))
      (node (ref "C18") (pin "2") (pinfunction "2_2") (pintype "passive"))
      (node (ref "R30") (pin "2") (pinfunction "2_2") (pintype "passive"))
    )
    (net (code "39") (name "Net-(ANALOG_MUX-CHAN14)") (class "Default")
      (node (ref "ANALOG_MUX") (pin "17") (pinfunction "CHAN14_17") (pintype "bidirectional"))
      (node (ref "C19") (pin "2") (pinfunction "2_2") (pintype "passive"))
      (node (ref "R31") (pin "2") (pinfunction "2_2") (pintype "passive"))
    )
    (net (code "40") (name "Net-(ANALOG_MUX-CHAN15)") (class "Default")
      (node (ref "ANALOG_MUX") (pin "16") (pinfunction "CHAN15_16") (pintype "bidirectional"))
      (node (ref "C20") (pin "2") (pinfunction "2_2") (pintype "passive"))
      (node (ref "R32") (pin "2") (pinfunction "2_2") (pintype "passive"))
    )
    (net (code "41") (name "Net-(D1-PadA)") (class "Default")
      (node (ref "D1") (pin "A") (pinfunction "A_A") (pintype "passive"))
      (node (ref "F1") (pin "1") (pinfunction "1_1") (pintype "bidirectional"))
    )
    (net (code "42") (name "Net-(D1-PadC)") (class "Default")
      (node (ref "D1") (pin "C") (pinfunction "C_C") (pintype "passive"))
      (node (ref "U$1") (pin "VIN") (pinfunction "VIN_VIN") (pintype "bidirectional"))
    )
    (net (code "43") (name "Net-(D2-PadA)") (class "Default")
      (node (ref "D2") (pin "A") (pinfunction "A_A") (pintype "passive"))
      (node (ref "F2") (pin "1") (pinfunction "1_1") (pintype "bidirectional"))
    )
    (net (code "44") (name "Net-(JP1G-Pad1)") (class "Default")
      (node (ref "JP1G") (pin "1") (pinfunction "1_1") (pintype "passive"))
      (node (ref "U$2") (pin "P$5") (pinfunction "P$5_P$5") (pintype "bidirectional"))
    )
    (net (code "45") (name "Net-(JP2G-Pad1)") (class "Default")
      (node (ref "JP2G") (pin "1") (pinfunction "1_1") (pintype "passive"))
      (node (ref "U$2") (pin "P$8") (pinfunction "P$8_P$8") (pintype "bidirectional"))
    )
    (net (code "46") (name "Net-(JP3G-Pad1)") (class "Default")
      (node (ref "JP3G") (pin "1") (pinfunction "1_1") (pintype "passive"))
      (node (ref "U$3") (pin "P$5") (pinfunction "P$5_P$5") (pintype "bidirectional"))
    )
    (net (code "47") (name "Net-(JP4G-Pad1)") (class "Default")
      (node (ref "JP4G") (pin "1") (pinfunction "1_1") (pintype "passive"))
      (node (ref "U$3") (pin "P$8") (pinfunction "P$8_P$8") (pintype "bidirectional"))
    )
    (net (code "48") (name "Net-(LED1-PadC)") (class "Default")
      (node (ref "LED1") (pin "C") (pinfunction "C_C") (pintype "passive"))
      (node (ref "R2") (pin "2") (pinfunction "2_2") (pintype "passive"))
    )
    (net (code "49") (name "Net-(LED2-PadC)") (class "Default")
      (node (ref "LED2") (pin "C") (pinfunction "C_C") (pintype "passive"))
      (node (ref "R3") (pin "2") (pinfunction "2_2") (pintype "passive"))
    )
    (net (code "50") (name "Net-(LED4-PadC)") (class "Default")
      (node (ref "LED4") (pin "C") (pinfunction "C_C") (pintype "passive"))
      (node (ref "R4") (pin "2") (pinfunction "2_2") (pintype "passive"))
    )
    (net (code "51") (name "Net-(Q1-D)") (class "Default")
      (node (ref "Q1") (pin "3") (pinfunction "D_3") (pintype "bidirectional"))
      (node (ref "U$3") (pin "P$12") (pinfunction "COIL12_P$12") (pintype "bidirectional"))
    )
    (net (code "52") (name "Net-(Q1-G)") (class "Default")
      (node (ref "Q1") (pin "1") (pinfunction "G_1") (pintype "bidirectional"))
      (node (ref "R5") (pin "1") (pinfunction "1_1") (pintype "passive"))
    )
    (net (code "53") (name "Net-(Q4-D)") (class "Default")
      (node (ref "Q4") (pin "3") (pinfunction "D_3") (pintype "bidirectional"))
      (node (ref "U$2") (pin "P$12") (pinfunction "COIL12_P$12") (pintype "bidirectional"))
    )
    (net (code "54") (name "Net-(Q4-G)") (class "Default")
      (node (ref "Q4") (pin "1") (pinfunction "G_1") (pintype "bidirectional"))
      (node (ref "R9") (pin "1") (pinfunction "1_1") (pintype "passive"))
    )
    (net (code "55") (name "Net-(U$4A-C1+)") (class "Default")
      (node (ref "C25") (pin "1") (pinfunction "1_1") (pintype "passive"))
      (node (ref "U$4") (pin "2") (pinfunction "C1+_2") (pintype "passive"))
    )
    (net (code "56") (name "Net-(U$4A-C1-)") (class "Default")
      (node (ref "C25") (pin "2") (pinfunction "2_2") (pintype "passive"))
      (node (ref "U$4") (pin "4") (pinfunction "C1-_4") (pintype "passive"))
    )
    (net (code "57") (name "Net-(U$4A-C2+)") (class "Default")
      (node (ref "C30") (pin "1") (pinfunction "1_1") (pintype "passive"))
      (node (ref "U$4") (pin "5") (pinfunction "C2+_5") (pintype "passive"))
    )
    (net (code "58") (name "Net-(U$4A-C2-)") (class "Default")
      (node (ref "C30") (pin "2") (pinfunction "2_2") (pintype "passive"))
      (node (ref "U$4") (pin "6") (pinfunction "C2-_6") (pintype "passive"))
    )
    (net (code "59") (name "Net-(U$4A-V+)") (class "Default")
      (node (ref "C32") (pin "2") (pinfunction "2_2") (pintype "passive"))
      (node (ref "U$4") (pin "3") (pinfunction "V+_3") (pintype "passive"))
    )
    (net (code "60") (name "Net-(U$4A-V-)") (class "Default")
      (node (ref "C31") (pin "1") (pinfunction "1_1") (pintype "passive"))
      (node (ref "U$4") (pin "7") (pinfunction "V-_7") (pintype "passive"))
    )
    (net (code "61") (name "RI1") (class "Default")
      (node (ref "CEL1") (pin "3") (pinfunction "CMU3_3") (pintype "bidirectional"))
      (node (ref "U$1") (pin "TX2") (pinfunction "TX2_TX2") (pintype "bidirectional"))
    )
    (net (code "62") (name "RI2") (class "Default")
      (node (ref "CEL2") (pin "3") (pinfunction "CMU3_3") (pintype "bidirectional"))
      (node (ref "U$1") (pin "TX3") (pinfunction "TX3_TX3") (pintype "bidirectional"))
    )
    (net (code "63") (name "RI3") (class "Default")
      (node (ref "CEL3") (pin "3") (pinfunction "CMU3_3") (pintype "bidirectional"))
      (node (ref "U$1") (pin "10") (pinfunction "10_10") (pintype "bidirectional"))
    )
    (net (code "64") (name "RI4") (class "Default")
      (node (ref "CEL4") (pin "3") (pinfunction "CMU3_3") (pintype "bidirectional"))
      (node (ref "U$1") (pin "12") (pinfunction "12_12") (pintype "bidirectional"))
    )
    (net (code "65") (name "RO1") (class "Default")
      (node (ref "CEL1") (pin "5") (pinfunction "CMU5_5") (pintype "bidirectional"))
      (node (ref "U$1") (pin "RX2") (pinfunction "RX2_RX2") (pintype "bidirectional"))
    )
    (net (code "66") (name "RO2") (class "Default")
      (node (ref "CEL2") (pin "5") (pinfunction "CMU5_5") (pintype "bidirectional"))
      (node (ref "U$1") (pin "RX3") (pinfunction "RX3_RX3") (pintype "bidirectional"))
    )
    (net (code "67") (name "RO3") (class "Default")
      (node (ref "CEL3") (pin "5") (pinfunction "CMU5_5") (pintype "bidirectional"))
      (node (ref "U$1") (pin "9") (pinfunction "9_9") (pintype "bidirectional"))
    )
    (net (code "68") (name "RO4") (class "Default")
      (node (ref "CEL4") (pin "5") (pinfunction "CMU5_5") (pintype "bidirectional"))
      (node (ref "U$1") (pin "11") (pinfunction "11_11") (pintype "bidirectional"))
    )
    (net (code "69") (name "RX") (class "Default")
      (node (ref "U$4") (pin "14") (pinfunction "R1IN_14") (pintype "input"))
      (node (ref "X2") (pin "2") (pinfunction "2_2") (pintype "passive"))
    )
    (net (code "70") (name "RX1") (class "Default")
      (node (ref "U$1") (pin "RX1") (pinfunction "RX1_RX1") (pintype "bidirectional"))
      (node (ref "U$4") (pin "13") (pinfunction "R1OUT_13") (pintype "output"))
    )
    (net (code "71") (name "SCRN_PWR") (class "Default")
      (node (ref "D2") (pin "C") (pinfunction "C_C") (pintype "passive"))
      (node (ref "X2") (pin "4") (pinfunction "4_4") (pintype "passive"))
      (node (ref "X2") (pin "7") (pinfunction "7_7") (pintype "passive"))
      (node (ref "X2") (pin "8") (pinfunction "8_8") (pintype "passive"))
    )
    (net (code "72") (name "SHDN") (class "Default")
      (node (ref "U$1") (pin "2") (pinfunction "2_2") (pintype "bidirectional"))
      (node (ref "U$4") (pin "18") (pinfunction "SHDN/_18") (pintype "input"))
    )
    (net (code "73") (name "TS1") (class "Default")
      (node (ref "CEL1") (pin "6") (pinfunction "CMU6_6") (pintype "bidirectional"))
      (node (ref "R7") (pin "1") (pinfunction "1_1") (pintype "passive"))
    )
    (net (code "74") (name "TS2") (class "Default")
      (node (ref "CEL2") (pin "6") (pinfunction "CMU6_6") (pintype "bidirectional"))
      (node (ref "R21") (pin "1") (pinfunction "1_1") (pintype "passive"))
    )
    (net (code "75") (name "TS3") (class "Default")
      (node (ref "CEL3") (pin "6") (pinfunction "CMU6_6") (pintype "bidirectional"))
      (node (ref "R25") (pin "1") (pinfunction "1_1") (pintype "passive"))
    )
    (net (code "76") (name "TS4") (class "Default")
      (node (ref "CEL4") (pin "6") (pinfunction "CMU6_6") (pintype "bidirectional"))
      (node (ref "R29") (pin "1") (pinfunction "1_1") (pintype "passive"))
    )
    (net (code "77") (name "TS_CON") (class "Default")
      (node (ref "C24") (pin "1") (pinfunction "1_1") (pintype "passive"))
      (node (ref "LMT87") (pin "OUT") (pinfunction "OUT_OUT") (pintype "bidirectional"))
      (node (ref "U$1") (pin "A6") (pinfunction "A6_A6") (pintype "bidirectional"))
    )
    (net (code "78") (name "TX") (class "Default")
      (node (ref "U$4") (pin "15") (pinfunction "T1OUT_15") (pintype "output"))
      (node (ref "X2") (pin "3") (pinfunction "3_3") (pintype "passive"))
    )
    (net (code "79") (name "TX1") (class "Default")
      (node (ref "U$1") (pin "TX1") (pinfunction "TX1_TX1") (pintype "bidirectional"))
      (node (ref "U$4") (pin "12") (pinfunction "T1IN_12") (pintype "input"))
    )
    (net (code "80") (name "VS1") (class "Default")
      (node (ref "CEL1") (pin "7") (pinfunction "CMU7_7") (pintype "bidirectional"))
      (node (ref "R13") (pin "1") (pinfunction "1_1") (pintype "passive"))
    )
    (net (code "81") (name "VS2") (class "Default")
      (node (ref "CEL2") (pin "7") (pinfunction "CMU7_7") (pintype "bidirectional"))
      (node (ref "R24") (pin "1") (pinfunction "1_1") (pintype "passive"))
    )
    (net (code "82") (name "VS3") (class "Default")
      (node (ref "CEL3") (pin "7") (pinfunction "CMU7_7") (pintype "bidirectional"))
      (node (ref "R28") (pin "1") (pinfunction "1_1") (pintype "passive"))
    )
    (net (code "83") (name "VS4") (class "Default")
      (node (ref "CEL4") (pin "7") (pinfunction "CMU7_7") (pintype "bidirectional"))
      (node (ref "R32") (pin "1") (pinfunction "1_1") (pintype "passive"))
    )
    (net (code "84") (name "unconnected-(U$1-Pad3V3)") (class "Default")
      (node (ref "U$1") (pin "3V3") (pinfunction "3V3_3V3") (pintype "bidirectional"))
    )
    (net (code "85") (name "unconnected-(U$1-Pad5)") (class "Default")
      (node (ref "U$1") (pin "5") (pinfunction "5_5") (pintype "bidirectional"))
    )
    (net (code "86") (name "unconnected-(U$1-Pad5V)") (class "Default")
      (node (ref "U$1") (pin "5V") (pinfunction "5V_5V") (pintype "bidirectional"))
    )
    (net (code "87") (name "unconnected-(U$1-Pad6)") (class "Default")
      (node (ref "U$1") (pin "6") (pinfunction "6_6") (pintype "bidirectional"))
    )
    (net (code "88") (name "unconnected-(U$1-Pad7)") (class "Default")
      (node (ref "U$1") (pin "7") (pinfunction "7_7") (pintype "bidirectional"))
    )
    (net (code "89") (name "unconnected-(U$1-Pad8)") (class "Default")
      (node (ref "U$1") (pin "8") (pinfunction "8_8") (pintype "bidirectional"))
    )
    (net (code "90") (name "unconnected-(U$1-Pad13)") (class "Default")
      (node (ref "U$1") (pin "13") (pinfunction "13_13") (pintype "bidirectional"))
    )
    (net (code "91") (name "unconnected-(U$1-PadA7)") (class "Default")
      (node (ref "U$1") (pin "A7") (pinfunction "A7_A7") (pintype "bidirectional"))
    )
    (net (code "92") (name "unconnected-(U$1-PadA10)") (class "Default")
      (node (ref "U$1") (pin "A10") (pinfunction "A10_A10") (pintype "bidirectional"))
    )
    (net (code "93") (name "unconnected-(U$1-PadA11)") (class "Default")
      (node (ref "U$1") (pin "A11") (pinfunction "A11_A11") (pintype "bidirectional"))
    )
    (net (code "94") (name "unconnected-(U$1-PadAREF)") (class "Default")
      (node (ref "U$1") (pin "AREF") (pinfunction "AREF_AREF") (pintype "bidirectional"))
    )
    (net (code "95") (name "unconnected-(U$1-PadCANRX)") (class "Default")
      (node (ref "U$1") (pin "CANRX") (pinfunction "CANRX_CANRX") (pintype "bidirectional"))
    )
    (net (code "96") (name "unconnected-(U$1-PadCANTX)") (class "Default")
      (node (ref "U$1") (pin "CANTX") (pinfunction "CANTX_CANTX") (pintype "bidirectional"))
    )
    (net (code "97") (name "unconnected-(U$1-PadDAC0)") (class "Default")
      (node (ref "U$1") (pin "DAC0") (pinfunction "DAC0_DAC0") (pintype "bidirectional"))
    )
    (net (code "98") (name "unconnected-(U$1-PadDAC1)") (class "Default")
      (node (ref "U$1") (pin "DAC1") (pinfunction "DAC1_DAC1") (pintype "bidirectional"))
    )
    (net (code "99") (name "unconnected-(U$1-PadIOREF)") (class "Default")
      (node (ref "U$1") (pin "IOREF") (pinfunction "IOREF_IOREF") (pintype "bidirectional"))
    )
    (net (code "100") (name "unconnected-(U$1-PadNC)") (class "Default")
      (node (ref "U$1") (pin "NC") (pinfunction "NC_NC") (pintype "bidirectional"))
    )
    (net (code "101") (name "unconnected-(U$1-PadRESET)") (class "Default")
      (node (ref "U$1") (pin "RESET") (pinfunction "RESET_RESET") (pintype "bidirectional"))
    )
    (net (code "102") (name "unconnected-(U$1-PadRX0)") (class "Default")
      (node (ref "U$1") (pin "RX0") (pinfunction "RX0_RX0") (pintype "bidirectional"))
    )
    (net (code "103") (name "unconnected-(U$1-PadSCL)") (class "Default")
      (node (ref "U$1") (pin "SCL") (pinfunction "SCL_SCL") (pintype "bidirectional"))
    )
    (net (code "104") (name "unconnected-(U$1-PadSCL1)") (class "Default")
      (node (ref "U$1") (pin "SCL1") (pinfunction "SCL1_SCL1") (pintype "bidirectional"))
    )
    (net (code "105") (name "unconnected-(U$1-PadSDA)") (class "Default")
      (node (ref "U$1") (pin "SDA") (pinfunction "SDA_SDA") (pintype "bidirectional"))
    )
    (net (code "106") (name "unconnected-(U$1-PadSDA1)") (class "Default")
      (node (ref "U$1") (pin "SDA1") (pinfunction "SDA1_SDA1") (pintype "bidirectional"))
    )
    (net (code "107") (name "unconnected-(U$1-PadTX0)") (class "Default")
      (node (ref "U$1") (pin "TX0") (pinfunction "TX0_TX0") (pintype "bidirectional"))
    )
    (net (code "108") (name "unconnected-(U$4A-R2OUT-Pad10)") (class "Default")
      (node (ref "U$4") (pin "10") (pinfunction "R2OUT_10") (pintype "output"))
    )
    (net (code "109") (name "unconnected-(U$4A-T2OUT-Pad8)") (class "Default")
      (node (ref "U$4") (pin "8") (pinfunction "T2OUT_8") (pintype "output"))
    )
    (net (code "110") (name "~{RES_CEL_1&2}") (class "Default")
      (node (ref "R9") (pin "2") (pinfunction "2_2") (pintype "passive"))
      (node (ref "U$1") (pin "4") (pinfunction "4_4") (pintype "bidirectional"))
    )
    (net (code "111") (name "~{RES_CEL_3&4}") (class "Default")
      (node (ref "R5") (pin "2") (pinfunction "2_2") (pintype "passive"))
      (node (ref "U$1") (pin "3") (pinfunction "3_3") (pintype "bidirectional"))
    )
  )
)
